# main2.net
KiCad netlist of a schematic drawn in EAGLE
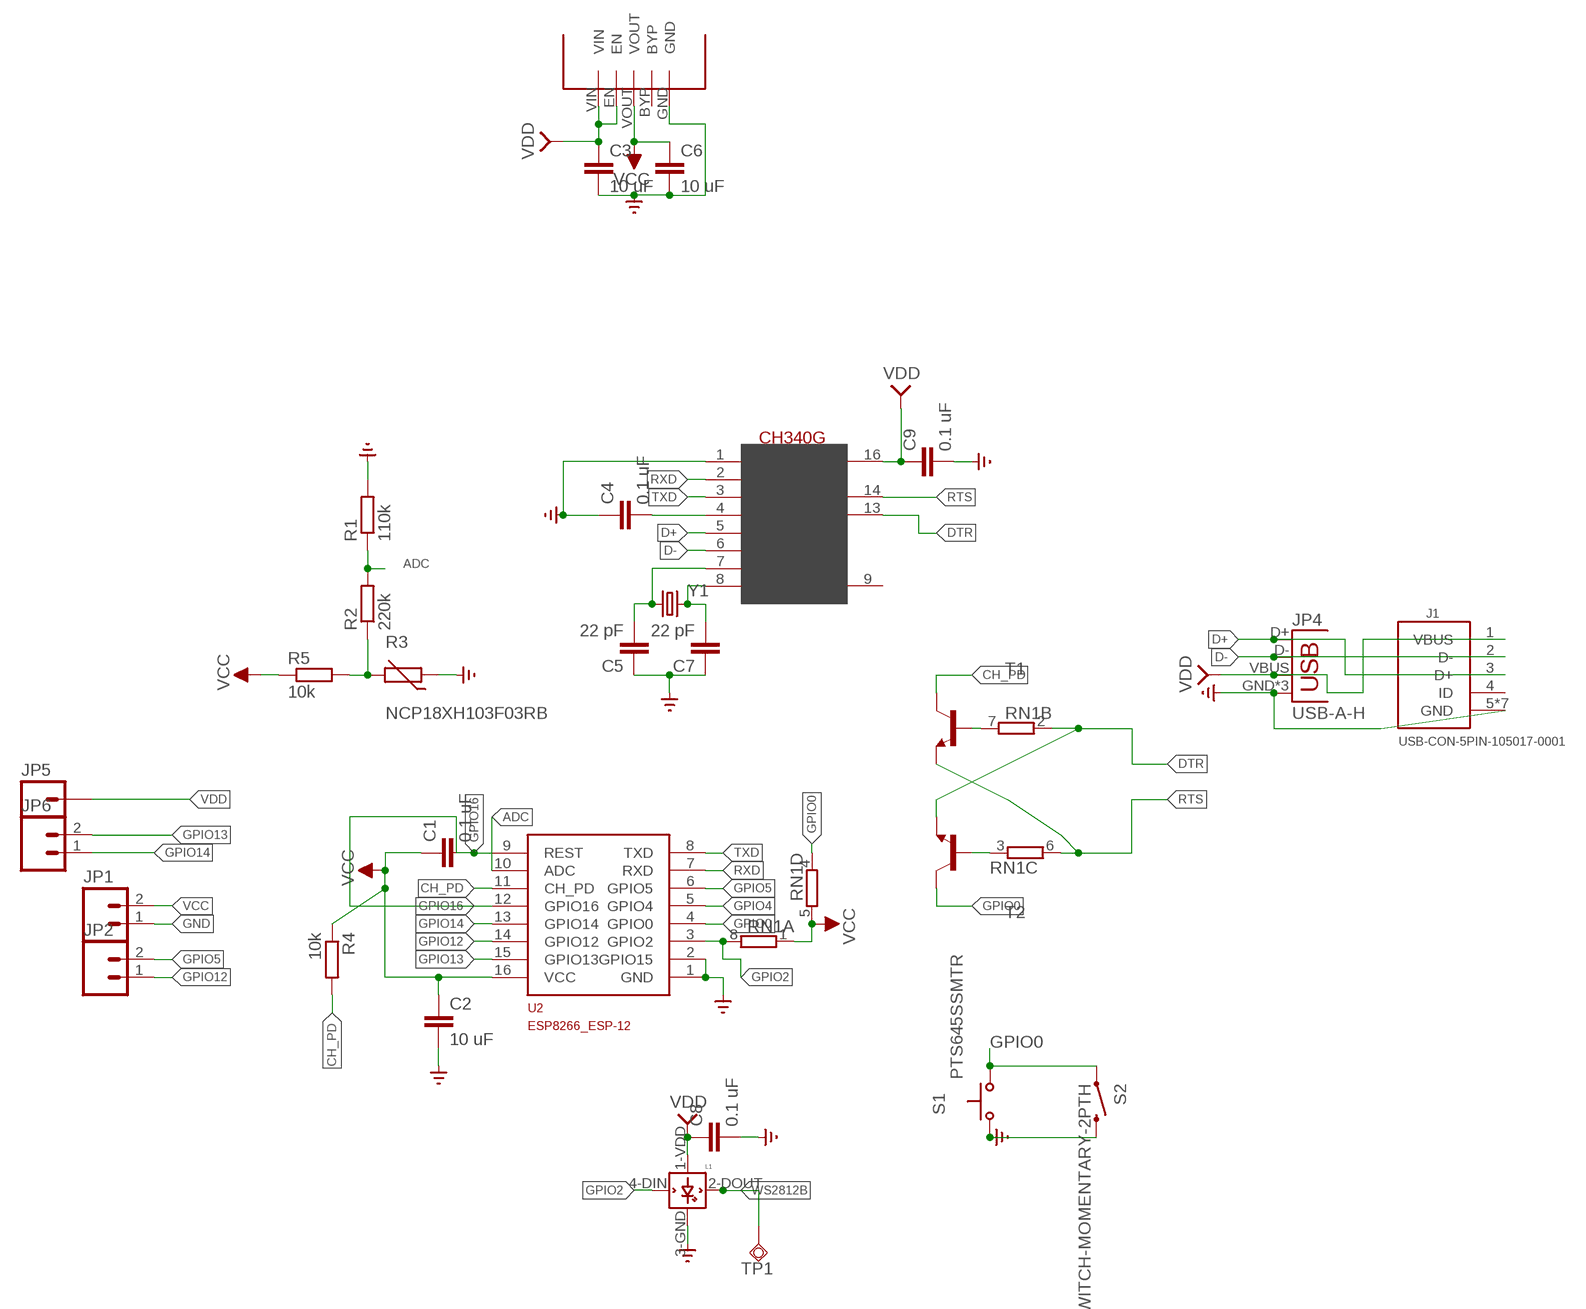
[diagram p0: schematic, sheet 1]

(export (version "E")
  (design (tool "Eeschema 10.0.6"))
  (components
    (comp (ref "C1")
      (value "0.1 uF")
      (footprint "eagle-import:C0603K")
      (libsource (lib "eagle-import") (part "C-EUC0603K"))
    )
    (comp (ref "C2")
      (value "10 uF")
      (footprint "eagle-import:C0603K")
      (libsource (lib "eagle-import") (part "C-EUC0603K"))
    )
    (comp (ref "C3")
      (value "10 uF")
      (footprint "eagle-import:C0603K")
      (libsource (lib "eagle-import") (part "C-EUC0603K"))
    )
    (comp (ref "C4")
      (value "0.1 uF")
      (footprint "eagle-import:C0603K")
      (libsource (lib "eagle-import") (part "C-EUC0603K"))
    )
    (comp (ref "C5")
      (value "22 pF")
      (footprint "eagle-import:C0805K")
      (libsource (lib "eagle-import") (part "C-EUC0805K"))
    )
    (comp (ref "C6")
      (value "10 uF")
      (footprint "eagle-import:C0603K")
      (libsource (lib "eagle-import") (part "C-EUC0603K"))
    )
    (comp (ref "C7")
      (value "22 pF")
      (footprint "eagle-import:C0805K")
      (libsource (lib "eagle-import") (part "C-EUC0805K"))
    )
    (comp (ref "C8")
      (value "0.1 uF")
      (footprint "eagle-import:C0603K")
      (libsource (lib "eagle-import") (part "C-EUC0603K"))
    )
    (comp (ref "C9")
      (value "0.1 uF")
      (footprint "eagle-import:C0603K")
      (libsource (lib "eagle-import") (part "C-EUC0603K"))
    )
    (comp (ref "J1")
      (value "USB-CON-5PIN-105017-0001")
      (footprint "eagle-import:USB-MICRO-MOLEX-105017-0001")
      (libsource (lib "eagle-import") (part "USB-CON-5PIN-105017-0001"))
    )
    (comp (ref "JP1")
      (value "M02LOCK")
      (footprint "eagle-import:1X02_LOCK")
      (libsource (lib "eagle-import") (part "M02LOCK"))
    )
    (comp (ref "JP2")
      (value "M02LOCK")
      (footprint "eagle-import:1X02_LOCK")
      (libsource (lib "eagle-import") (part "M02LOCK"))
    )
    (comp (ref "JP4")
      (value "USB-A-H")
      (footprint "eagle-import:USB-A-H")
      (libsource (lib "eagle-import") (part "USB-A-H"))
    )
    (comp (ref "JP5")
      (value "M01PTH")
      (footprint "eagle-import:1X01")
      (libsource (lib "eagle-import") (part "M01PTH"))
    )
    (comp (ref "JP6")
      (value "M02LOCK")
      (footprint "eagle-import:1X02_LOCK")
      (libsource (lib "eagle-import") (part "M02LOCK"))
    )
    (comp (ref "L1")
      (value "WS2812B")
      (footprint "eagle-import:WS2812B")
      (libsource (lib "eagle-import") (part "WS2812B"))
    )
    (comp (ref "R1")
      (value "110k")
      (footprint "eagle-import:R0603")
      (libsource (lib "eagle-import") (part "R-EU_R0603"))
    )
    (comp (ref "R2")
      (value "220k")
      (footprint "eagle-import:R0603")
      (libsource (lib "eagle-import") (part "R-EU_R0603"))
    )
    (comp (ref "R3")
      (value "NCP18XH103F03RB")
      (footprint "eagle-import:0603-RES")
      (libsource (lib "eagle-import") (part "NCP18XH103F03RB"))
    )
    (comp (ref "R4")
      (value "10k")
      (footprint "eagle-import:R0805")
      (libsource (lib "eagle-import") (part "R-EU_R0805"))
    )
    (comp (ref "R5")
      (value "10k")
      (footprint "eagle-import:R0805")
      (libsource (lib "eagle-import") (part "R-EU_R0805"))
    )
    (comp (ref "RN1")
      (value "4R-NEXB38V")
      (footprint "eagle-import:EXB38V")
      (libsource (lib "eagle-import") (part "4R-NEXB38V"))
    )
    (comp (ref "S1")
      (value "PTS645SSMTR")
      (footprint "eagle-import:PTS645-SMD")
      (libsource (lib "eagle-import") (part "PTS645S???SMTR"))
    )
    (comp (ref "S2")
      (value "SWITCH-MOMENTARY-2PTH")
      (footprint "eagle-import:TACTILE-PTH")
      (libsource (lib "eagle-import") (part "SWITCH-MOMENTARY-2PTH"))
    )
    (comp (ref "T1")
      (value "MMBT2222ALT1-NPN-SOT23-BEC")
      (footprint "eagle-import:SOT23-BEC")
      (libsource (lib "eagle-import") (part "-NPN-SOT23-BECMMBT2222ALT1"))
    )
    (comp (ref "T2")
      (value "MMBT2222ALT1-NPN-SOT23-BEC")
      (footprint "eagle-import:SOT23-BEC")
      (libsource (lib "eagle-import") (part "-NPN-SOT23-BECMMBT2222ALT1"))
    )
    (comp (ref "TP1")
      (value "TPSQTP20SQ")
      (footprint "eagle-import:TP20SQ")
      (libsource (lib "eagle-import") (part "TPSQTP20SQ"))
    )
    (comp (ref "U1")
      (value "SPX3819")
      (footprint "eagle-import:SOT23-5L")
      (libsource (lib "eagle-import") (part "SPX3819"))
    )
    (comp (ref "U2")
      (value "ESP8266_ESP-12")
      (footprint "eagle-import:ESP8266-ESP12")
      (libsource (lib "eagle-import") (part "ESP8266_ESP-12"))
    )
    (comp (ref "U3")
      (value "CH340G")
      (footprint "eagle-import:SOIC16")
      (libsource (lib "eagle-import") (part "CH340G"))
    )
    (comp (ref "Y1")
      (value "CRYSTALSM49")
      (footprint "eagle-import:SM49")
      (libsource (lib "eagle-import") (part "CRYSTALSM49"))
    )
  )
  (nets
    (net (code "1") (name "ADC") (class "Default")
      (node (ref "R1") (pin "1") (pinfunction "1_1") (pintype "passive"))
      (node (ref "R2") (pin "2") (pinfunction "2_2") (pintype "passive"))
      (node (ref "U2") (pin "10") (pinfunction "ADC_10") (pintype "bidirectional"))
    )
    (net (code "2") (name "CH_PD") (class "Default")
      (node (ref "R4") (pin "2") (pinfunction "2_2") (pintype "passive"))
      (node (ref "T1") (pin "C") (pinfunction "C_C") (pintype "passive"))
      (node (ref "U2") (pin "11") (pinfunction "CH_PD_11") (pintype "bidirectional"))
    )
    (net (code "3") (name "D+") (class "Default")
      (node (ref "J1") (pin "3") (pinfunction "D+_3") (pintype "bidirectional"))
      (node (ref "JP4") (pin "D+") (pinfunction "D+_D+") (pintype "bidirectional"))
      (node (ref "U3") (pin "5") (pinfunction "D+_5") (pintype "bidirectional"))
    )
    (net (code "4") (name "D-") (class "Default")
      (node (ref "J1") (pin "2") (pinfunction "D-_2") (pintype "bidirectional"))
      (node (ref "JP4") (pin "D-") (pinfunction "D-_D-") (pintype "bidirectional"))
      (node (ref "U3") (pin "6") (pinfunction "D-_6") (pintype "bidirectional"))
    )
    (net (code "5") (name "DTR") (class "Default")
      (node (ref "RN1") (pin "2") (pinfunction "1_2") (pintype "passive"))
      (node (ref "T2") (pin "E") (pinfunction "E_E") (pintype "passive"))
      (node (ref "U3") (pin "13") (pinfunction "DTR_13") (pintype "bidirectional"))
    )
    (net (code "6") (name "GND") (class "Default")
      (node (ref "C2") (pin "2") (pinfunction "2_2") (pintype "passive"))
      (node (ref "C3") (pin "2") (pinfunction "2_2") (pintype "passive"))
      (node (ref "C4") (pin "1") (pinfunction "1_1") (pintype "passive"))
      (node (ref "C5") (pin "1") (pinfunction "1_1") (pintype "passive"))
      (node (ref "C6") (pin "2") (pinfunction "2_2") (pintype "passive"))
      (node (ref "C7") (pin "1") (pinfunction "1_1") (pintype "passive"))
      (node (ref "C8") (pin "2") (pinfunction "2_2") (pintype "passive"))
      (node (ref "C9") (pin "2") (pinfunction "2_2") (pintype "passive"))
      (node (ref "J1") (pin "5") (pinfunction "GND_5") (pintype "power_in"))
      (node (ref "J1") (pin "P$1") (pinfunction "GND_P$1") (pintype "power_in"))
      (node (ref "J1") (pin "P$2") (pinfunction "GND_P$2") (pintype "power_in"))
      (node (ref "J1") (pin "P$3") (pinfunction "GND_P$3") (pintype "power_in"))
      (node (ref "J1") (pin "P$4") (pinfunction "GND_P$4") (pintype "power_in"))
      (node (ref "J1") (pin "P$5") (pinfunction "GND_P$5") (pintype "power_in"))
      (node (ref "J1") (pin "P$6") (pinfunction "GND_P$6") (pintype "power_in"))
      (node (ref "JP1") (pin "1") (pinfunction "1_1") (pintype "passive"))
      (node (ref "JP4") (pin "GND") (pinfunction "GND_GND") (pintype "bidirectional"))
      (node (ref "JP4") (pin "GND2") (pinfunction "GND_GND2") (pintype "bidirectional"))
      (node (ref "JP4") (pin "GND3") (pinfunction "GND_GND3") (pintype "bidirectional"))
      (node (ref "L1") (pin "3-GND") (pinfunction "GND_3-GND") (pintype "bidirectional"))
      (node (ref "R1") (pin "2") (pinfunction "2_2") (pintype "passive"))
      (node (ref "R3") (pin "1") (pinfunction "1_1") (pintype "passive"))
      (node (ref "S1") (pin "1") (pinfunction "P_1") (pintype "passive"))
      (node (ref "S1") (pin "2") (pinfunction "P_2") (pintype "passive"))
      (node (ref "S2") (pin "3") (pinfunction "2_3") (pintype "passive"))
      (node (ref "S2") (pin "4") (pinfunction "2_4") (pintype "passive"))
      (node (ref "U1") (pin "GND") (pinfunction "GND_GND") (pintype "bidirectional"))
      (node (ref "U2") (pin "1") (pinfunction "GND_1") (pintype "bidirectional"))
      (node (ref "U2") (pin "2") (pinfunction "GPIO15_2") (pintype "bidirectional"))
      (node (ref "U3") (pin "1") (pinfunction "GND_1") (pintype "bidirectional"))
    )
    (net (code "7") (name "GPIO0") (class "Default")
      (node (ref "RN1") (pin "4") (pinfunction "1_4") (pintype "passive"))
      (node (ref "S1") (pin "3") (pinfunction "S_3") (pintype "passive"))
      (node (ref "S1") (pin "4") (pinfunction "S_4") (pintype "passive"))
      (node (ref "S2") (pin "1") (pinfunction "1_1") (pintype "passive"))
      (node (ref "S2") (pin "2") (pinfunction "1_2") (pintype "passive"))
      (node (ref "T2") (pin "C") (pinfunction "C_C") (pintype "passive"))
      (node (ref "U2") (pin "4") (pinfunction "GPIO0_4") (pintype "bidirectional"))
    )
    (net (code "8") (name "GPIO2") (class "Default")
      (node (ref "L1") (pin "4-DIN") (pinfunction "DIN_4-DIN") (pintype "input"))
      (node (ref "RN1") (pin "8") (pinfunction "2_8") (pintype "passive"))
      (node (ref "U2") (pin "3") (pinfunction "GPIO2_3") (pintype "bidirectional"))
    )
    (net (code "9") (name "GPIO4") (class "Default")
      (node (ref "U2") (pin "5") (pinfunction "GPIO4_5") (pintype "bidirectional"))
    )
    (net (code "10") (name "GPIO5") (class "Default")
      (node (ref "JP2") (pin "2") (pinfunction "2_2") (pintype "passive"))
      (node (ref "U2") (pin "6") (pinfunction "GPIO5_6") (pintype "bidirectional"))
    )
    (net (code "11") (name "GPIO12") (class "Default")
      (node (ref "JP2") (pin "1") (pinfunction "1_1") (pintype "passive"))
      (node (ref "U2") (pin "14") (pinfunction "GPIO12_14") (pintype "bidirectional"))
    )
    (net (code "12") (name "GPIO13") (class "Default")
      (node (ref "JP6") (pin "2") (pinfunction "2_2") (pintype "passive"))
      (node (ref "U2") (pin "15") (pinfunction "GPIO13_15") (pintype "bidirectional"))
    )
    (net (code "13") (name "GPIO14") (class "Default")
      (node (ref "JP6") (pin "1") (pinfunction "1_1") (pintype "passive"))
      (node (ref "U2") (pin "13") (pinfunction "GPIO14_13") (pintype "bidirectional"))
    )
    (net (code "14") (name "GPIO16") (class "Default")
      (node (ref "C1") (pin "2") (pinfunction "2_2") (pintype "passive"))
      (node (ref "U2") (pin "12") (pinfunction "GPIO16_12") (pintype "bidirectional"))
      (node (ref "U2") (pin "9") (pinfunction "REST_9") (pintype "bidirectional"))
    )
    (net (code "15") (name "Net-(R2-Pad1)") (class "Default")
      (node (ref "R2") (pin "1") (pinfunction "1_1") (pintype "passive"))
      (node (ref "R3") (pin "2") (pinfunction "2_2") (pintype "passive"))
      (node (ref "R5") (pin "2") (pinfunction "2_2") (pintype "passive"))
    )
    (net (code "16") (name "Net-(RN1B-2)") (class "Default")
      (node (ref "RN1") (pin "7") (pinfunction "2_7") (pintype "passive"))
      (node (ref "T1") (pin "B") (pinfunction "B_B") (pintype "passive"))
    )
    (net (code "17") (name "Net-(RN1C-1)") (class "Default")
      (node (ref "RN1") (pin "3") (pinfunction "1_3") (pintype "passive"))
      (node (ref "T2") (pin "B") (pinfunction "B_B") (pintype "passive"))
    )
    (net (code "18") (name "Net-(U3-V3)") (class "Default")
      (node (ref "C4") (pin "2") (pinfunction "2_2") (pintype "passive"))
      (node (ref "U3") (pin "4") (pinfunction "V3_4") (pintype "bidirectional"))
    )
    (net (code "19") (name "Net-(U3-XI)") (class "Default")
      (node (ref "C5") (pin "2") (pinfunction "2_2") (pintype "passive"))
      (node (ref "U3") (pin "7") (pinfunction "XI_7") (pintype "bidirectional"))
      (node (ref "Y1") (pin "1") (pinfunction "1_1") (pintype "passive"))
    )
    (net (code "20") (name "Net-(U3-XO)") (class "Default")
      (node (ref "C7") (pin "2") (pinfunction "2_2") (pintype "passive"))
      (node (ref "U3") (pin "8") (pinfunction "XO_8") (pintype "bidirectional"))
      (node (ref "Y1") (pin "2") (pinfunction "2_2") (pintype "passive"))
    )
    (net (code "21") (name "RTS") (class "Default")
      (node (ref "RN1") (pin "6") (pinfunction "2_6") (pintype "passive"))
      (node (ref "T1") (pin "E") (pinfunction "E_E") (pintype "passive"))
      (node (ref "U3") (pin "14") (pinfunction "RTS_14") (pintype "bidirectional"))
    )
    (net (code "22") (name "RXD") (class "Default")
      (node (ref "U2") (pin "7") (pinfunction "RXD_7") (pintype "bidirectional"))
      (node (ref "U3") (pin "2") (pinfunction "TX_2") (pintype "bidirectional"))
    )
    (net (code "23") (name "TXD") (class "Default")
      (node (ref "U2") (pin "8") (pinfunction "TXD_8") (pintype "bidirectional"))
      (node (ref "U3") (pin "3") (pinfunction "RX_3") (pintype "bidirectional"))
    )
    (net (code "24") (name "VCC") (class "Default")
      (node (ref "C1") (pin "1") (pinfunction "1_1") (pintype "passive"))
      (node (ref "C2") (pin "1") (pinfunction "1_1") (pintype "passive"))
      (node (ref "C6") (pin "1") (pinfunction "1_1") (pintype "passive"))
      (node (ref "JP1") (pin "2") (pinfunction "2_2") (pintype "passive"))
      (node (ref "R4") (pin "1") (pinfunction "1_1") (pintype "passive"))
      (node (ref "R5") (pin "1") (pinfunction "1_1") (pintype "passive"))
      (node (ref "RN1") (pin "1") (pinfunction "1_1") (pintype "passive"))
      (node (ref "RN1") (pin "5") (pinfunction "2_5") (pintype "passive"))
      (node (ref "U1") (pin "VOUT") (pinfunction "VOUT_VOUT") (pintype "bidirectional"))
      (node (ref "U2") (pin "16") (pinfunction "VCC_16") (pintype "bidirectional"))
    )
    (net (code "25") (name "VDD") (class "Default")
      (node (ref "C3") (pin "1") (pinfunction "1_1") (pintype "passive"))
      (node (ref "C8") (pin "1") (pinfunction "1_1") (pintype "passive"))
      (node (ref "C9") (pin "1") (pinfunction "1_1") (pintype "passive"))
      (node (ref "J1") (pin "1") (pinfunction "VBUS_1") (pintype "power_in"))
      (node (ref "JP4") (pin "VBUS") (pinfunction "VBUS_VBUS") (pintype "bidirectional"))
      (node (ref "JP5") (pin "1") (pinfunction "1_1") (pintype "passive"))
      (node (ref "L1") (pin "1-VDD") (pinfunction "VDD_1-VDD") (pintype "bidirectional"))
      (node (ref "U1") (pin "EN") (pinfunction "EN_EN") (pintype "bidirectional"))
      (node (ref "U1") (pin "VIN") (pinfunction "VIN_VIN") (pintype "bidirectional"))
      (node (ref "U3") (pin "16") (pinfunction "VCC_16") (pintype "bidirectional"))
    )
    (net (code "26") (name "WS2812B") (class "Default")
      (node (ref "L1") (pin "2-DOUT") (pinfunction "DOUT_2-DOUT") (pintype "output"))
      (node (ref "TP1") (pin "TP") (pinfunction "TP_TP") (pintype "input"))
    )
    (net (code "27") (name "unconnected-(J1-ID-Pad4)") (class "Default")
      (node (ref "J1") (pin "4") (pinfunction "ID_4") (pintype "bidirectional"))
    )
    (net (code "28") (name "unconnected-(U1-PadBYP)") (class "Default")
      (node (ref "U1") (pin "BYP") (pinfunction "BYP_BYP") (pintype "bidirectional"))
    )
    (net (code "29") (name "unconnected-(U3-CTS-Pad9)") (class "Default")
      (node (ref "U3") (pin "9") (pinfunction "CTS_9") (pintype "bidirectional"))
    )
  )
)
